# RJ45.net
KiCad netlist of a schematic drawn in Altium Designer
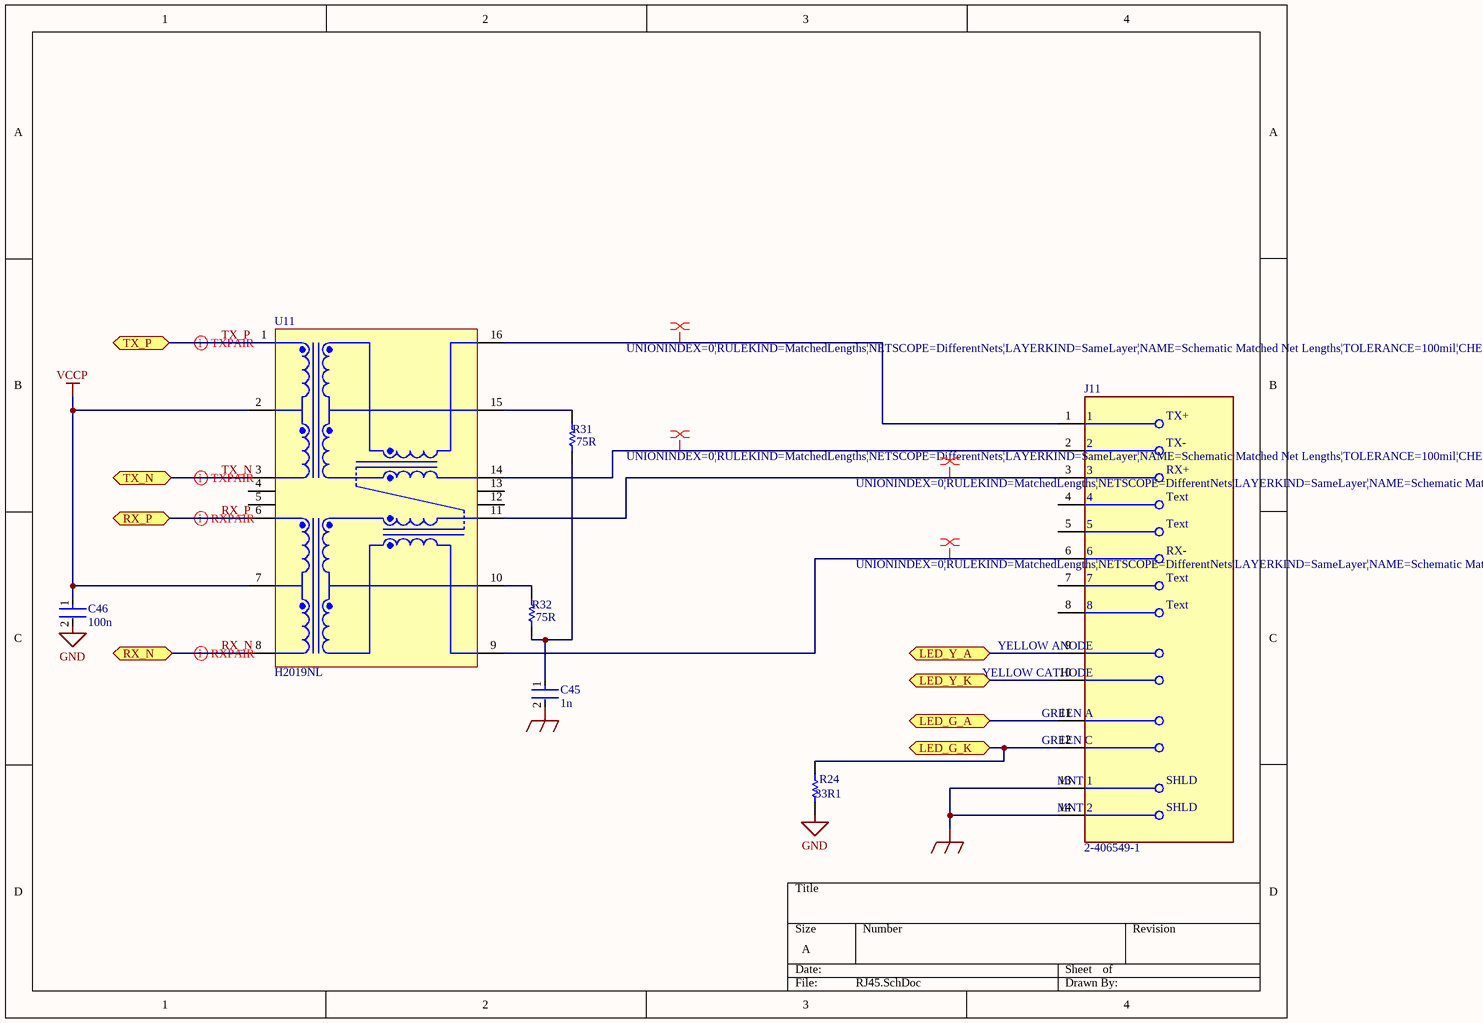
[diagram p0: RJ45.SchDoc]

(export (version "E")
  (design (tool "Eeschema 10.0.6"))
  (components
    (comp (ref "C45")
      (value "1n")
      (footprint "FP-GRM033-0_03-MFG")
      (description "Chip Multilayer Ceramic Capacitors for General Purpose, 0201, 0.10uF, X5R, 15%, 10%, 6.3V")
      (fields (field (name "VOLTAGE") "6.3V") (field (name "TOLERANCE") "10%"))
      (libsource (lib "Altium Content Vault") (part "b4654b650e69147ec39a6b967a45e02"))
    )
    (comp (ref "C46")
      (value "100n")
      (footprint "FP-GRM033-0_03-MFG")
      (description "Chip Multilayer Ceramic Capacitors for General Purpose, 0201, 0.10uF, X5R, 15%, 10%, 6.3V")
      (fields (field (name "VOLTAGE") "6.3V") (field (name "TOLERANCE") "10%"))
      (libsource (lib "Altium Content Vault") (part "b4654b650e69147ec39a6b967a45e02"))
    )
    (comp (ref "J11")
      (value "2-406549-1")
      (footprint "FP-2-406549-1-MFG")
      (description "CONN MOD JACK 8P8C R/A SHIELDED")
      (libsource (lib "Altium Content Vault") (part "5df2851a84d4daa1b10777dbcf9e12f"))
    )
    (comp (ref "R24")
      (value "33R1")
      (footprint "RESC1608X55X30LL20T20")
      (fields (field (name "PART NUMBER") "ERA3AEB301V") (field (name "MANUFACTURER") "Panasonic"))
      (libsource (lib "Altium Content Vault") (part "RES"))
    )
    (comp (ref "R31")
      (value "75R")
      (footprint "RESC1608X55X30LL20T20")
      (fields (field (name "PART NUMBER") "ERA3AEB301V") (field (name "MANUFACTURER") "Panasonic"))
      (libsource (lib "Altium Content Vault") (part "RES"))
    )
    (comp (ref "R32")
      (value "75R")
      (footprint "RESC1608X55X30LL20T20")
      (fields (field (name "PART NUMBER") "ERA3AEB301V") (field (name "MANUFACTURER") "Panasonic"))
      (libsource (lib "Altium Content Vault") (part "RES"))
    )
    (comp (ref "U11")
      (value "H2019NL")
      (footprint "PULS-H2019FNL_V")
      (description "Telecom Transformer, 100BASE-TX, 0 to 70 degC, 16-Pin SMD, RoHS")
      (fields (field (name "MANUFACTURER") "Pulse Electronics"))
      (libsource (lib "Altium Content Vault") (part "PULS-H2019FNL-16"))
    )
  )
  (nets
    (net (code "1") (name "/LED_G_A") (class "Default")
      (node (ref "J11") (pin "11") (pinfunction "GREEN_A_11") (pintype "passive"))
    )
    (net (code "3") (name "/LED_G_K") (class "Default")
      (node (ref "J11") (pin "12") (pinfunction "GREEN_C_12") (pintype "passive"))
      (node (ref "R24") (pin "2") (pinfunction "2_2") (pintype "passive"))
    )
    (net (code "4") (name "/LED_Y_A") (class "Default")
      (node (ref "J11") (pin "9") (pinfunction "YELLOW_ANODE_9") (pintype "passive"))
    )
    (net (code "5") (name "/LED_Y_K") (class "Default")
      (node (ref "J11") (pin "10") (pinfunction "YELLOW_CATHODE_10") (pintype "passive"))
    )
    (net (code "6") (name "/RX_N") (class "Default")
      (node (ref "U11") (pin "8") (pinfunction "RD-_8") (pintype "passive"))
    )
    (net (code "7") (name "/RX_P") (class "Default")
      (node (ref "U11") (pin "6") (pinfunction "RD+_6") (pintype "passive"))
    )
    (net (code "8") (name "/TX_N") (class "Default")
      (node (ref "U11") (pin "3") (pinfunction "TD-_3") (pintype "passive"))
    )
    (net (code "9") (name "/TX_P") (class "Default")
      (node (ref "U11") (pin "1") (pinfunction "TD+_1") (pintype "passive"))
    )
    (net (code "10") (name "GND") (class "Default")
      (node (ref "C45") (pin "2") (pinfunction "2_2") (pintype "passive"))
      (node (ref "C46") (pin "2") (pinfunction "2_2") (pintype "passive"))
      (node (ref "J11") (pin "13") (pinfunction "MNT_1_13") (pintype "passive"))
      (node (ref "J11") (pin "14") (pinfunction "MNT_2_14") (pintype "passive"))
      (node (ref "R24") (pin "1") (pinfunction "1_1") (pintype "passive"))
    )
    (net (code "11") (name "Net-(C45-Pad1)") (class "Default")
      (node (ref "C45") (pin "1") (pinfunction "1_1") (pintype "passive"))
      (node (ref "R31") (pin "1") (pinfunction "1_1") (pintype "passive"))
      (node (ref "R32") (pin "1") (pinfunction "1_1") (pintype "passive"))
    )
    (net (code "12") (name "Net-(U11-RX+)") (class "Default")
      (node (ref "J11") (pin "3") (pinfunction "3_3") (pintype "passive"))
      (node (ref "U11") (pin "11") (pinfunction "RX+_11") (pintype "passive"))
    )
    (net (code "13") (name "Net-(U11-RX-)") (class "Default")
      (node (ref "J11") (pin "6") (pinfunction "6_6") (pintype "passive"))
      (node (ref "U11") (pin "9") (pinfunction "RX-_9") (pintype "passive"))
    )
    (net (code "14") (name "Net-(U11-RXCT)") (class "Default")
      (node (ref "R32") (pin "2") (pinfunction "2_2") (pintype "passive"))
      (node (ref "U11") (pin "10") (pinfunction "RXCT_10") (pintype "passive"))
    )
    (net (code "15") (name "Net-(U11-TX+)") (class "Default")
      (node (ref "J11") (pin "1") (pinfunction "1_1") (pintype "passive"))
      (node (ref "U11") (pin "16") (pinfunction "TX+_16") (pintype "passive"))
    )
    (net (code "16") (name "Net-(U11-TX-)") (class "Default")
      (node (ref "J11") (pin "2") (pinfunction "2_2") (pintype "passive"))
      (node (ref "U11") (pin "14") (pinfunction "TX-_14") (pintype "passive"))
    )
    (net (code "17") (name "Net-(U11-TXCT)") (class "Default")
      (node (ref "R31") (pin "2") (pinfunction "2_2") (pintype "passive"))
      (node (ref "U11") (pin "15") (pinfunction "TXCT_15") (pintype "passive"))
    )
    (net (code "18") (name "VCCP") (class "Default")
      (node (ref "C46") (pin "1") (pinfunction "1_1") (pintype "passive"))
      (node (ref "U11") (pin "2") (pinfunction "TCT_2") (pintype "passive"))
      (node (ref "U11") (pin "7") (pinfunction "RCT_7") (pintype "passive"))
    )
    (net (code "19") (name "unconnected-(J11-Pad4)") (class "Default")
      (node (ref "J11") (pin "4") (pinfunction "4_4") (pintype "passive"))
    )
    (net (code "20") (name "unconnected-(J11-Pad5)") (class "Default")
      (node (ref "J11") (pin "5") (pinfunction "5_5") (pintype "passive"))
    )
    (net (code "21") (name "unconnected-(J11-Pad7)") (class "Default")
      (node (ref "J11") (pin "7") (pinfunction "7_7") (pintype "passive"))
    )
    (net (code "22") (name "unconnected-(J11-Pad8)") (class "Default")
      (node (ref "J11") (pin "8") (pinfunction "8_8") (pintype "passive"))
    )
    (net (code "23") (name "unconnected-(U11-NC-Pad4)") (class "Default")
      (node (ref "U11") (pin "4") (pinfunction "NC_4") (pintype "passive"))
    )
    (net (code "24") (name "unconnected-(U11-NC-Pad5)") (class "Default")
      (node (ref "U11") (pin "5") (pinfunction "NC_5") (pintype "passive"))
    )
    (net (code "25") (name "unconnected-(U11-NC-Pad12)") (class "Default")
      (node (ref "U11") (pin "12") (pinfunction "NC_12") (pintype "passive"))
    )
    (net (code "26") (name "unconnected-(U11-NC-Pad13)") (class "Default")
      (node (ref "U11") (pin "13") (pinfunction "NC_13") (pintype "passive"))
    )
  )
)
